# All_in_one_Starter_Kit_for_Arduino_V1_0.net
KiCad netlist of a schematic drawn in EAGLE
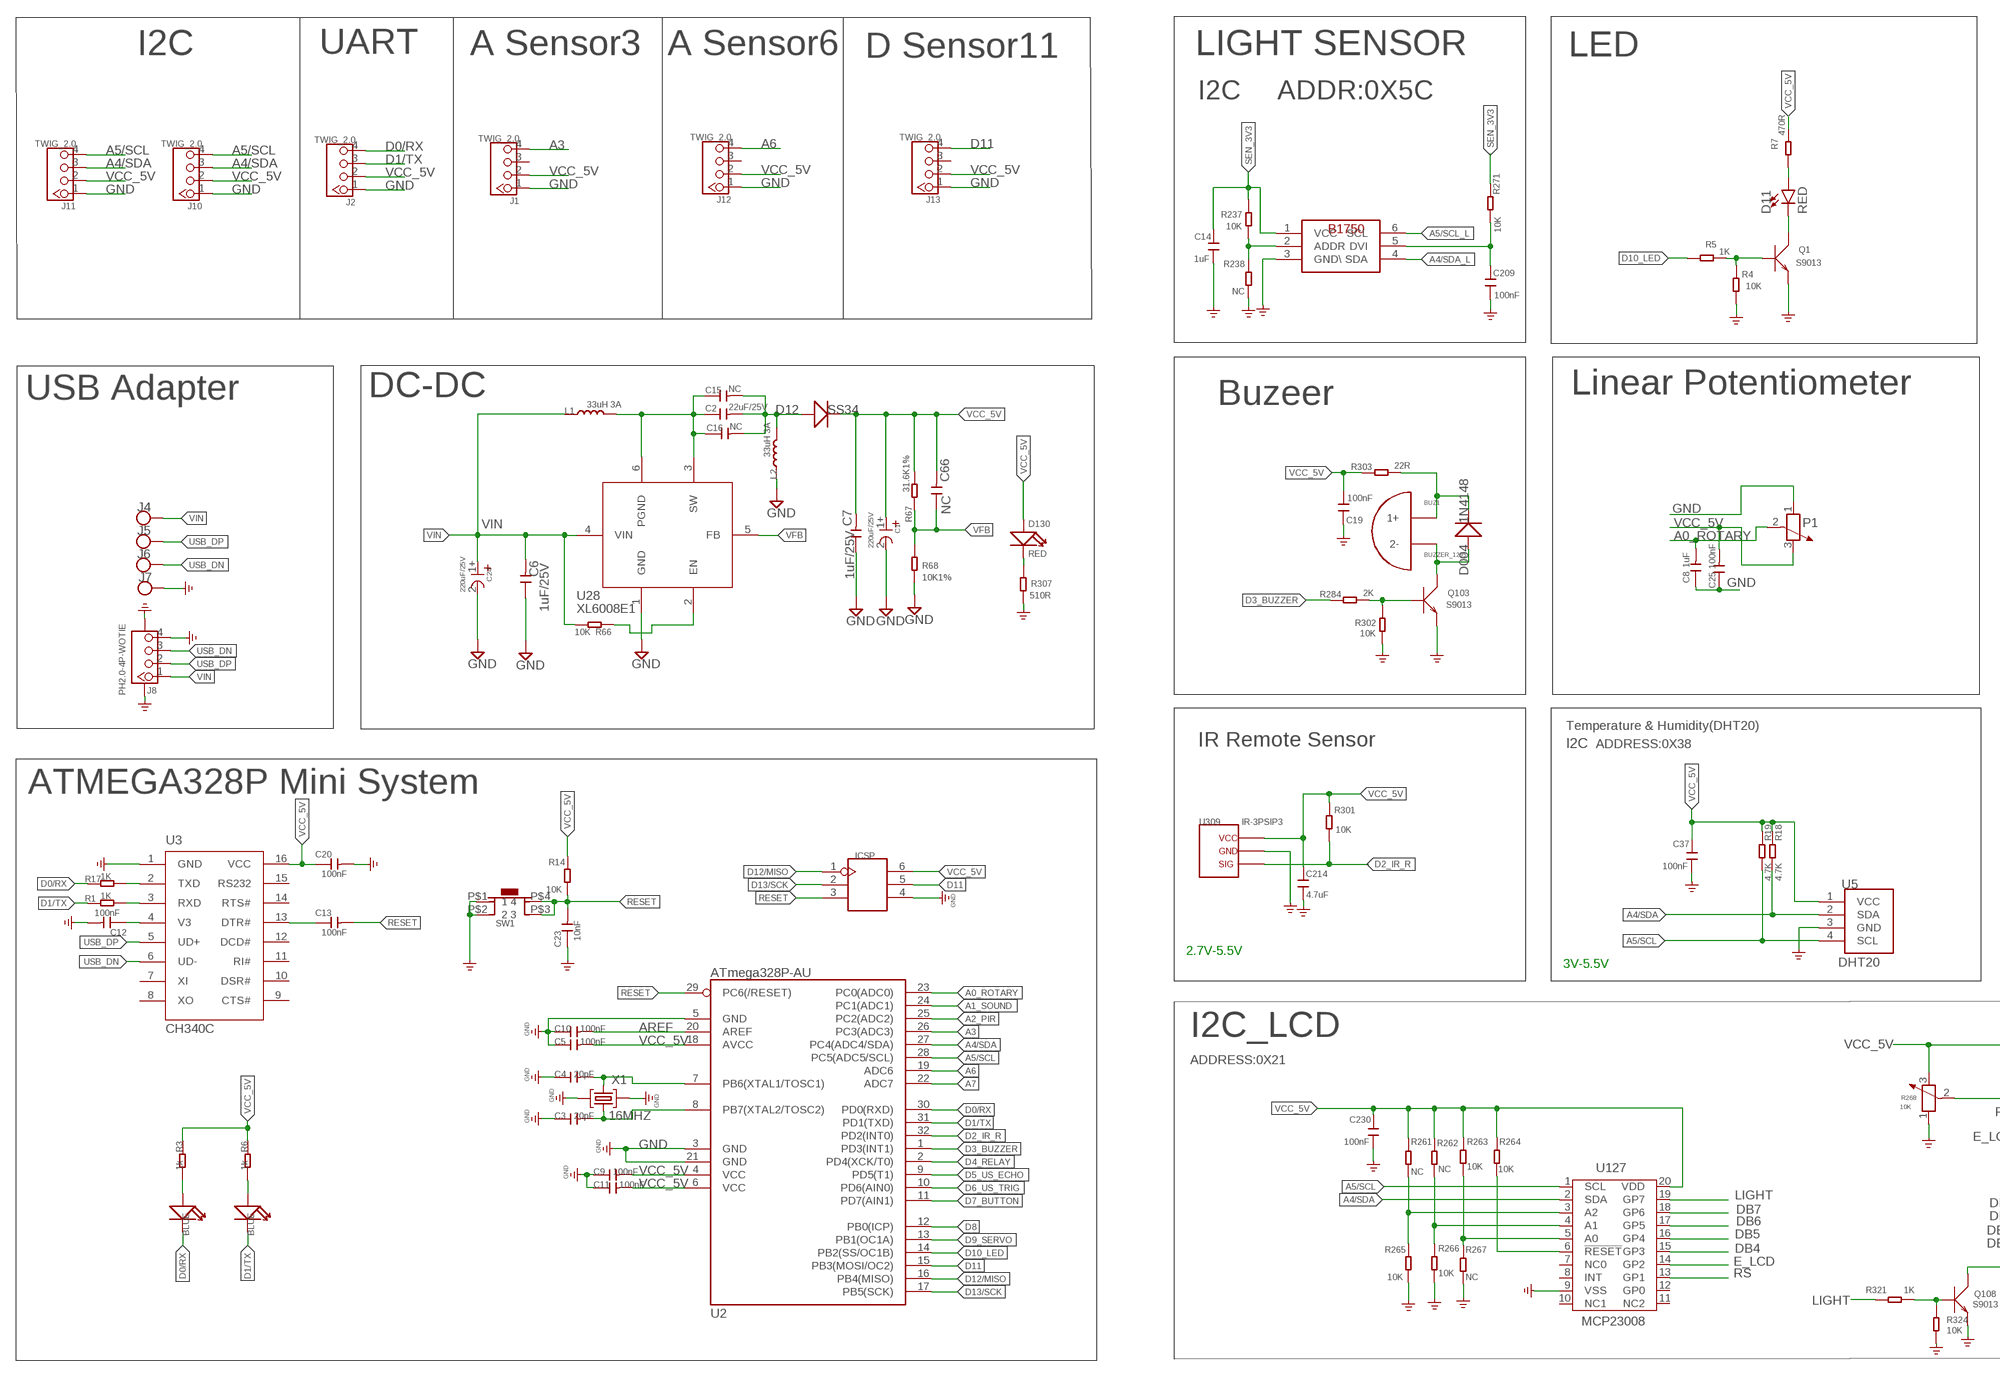
[diagram p0: schematic, sheet 1, part 1 of 2]
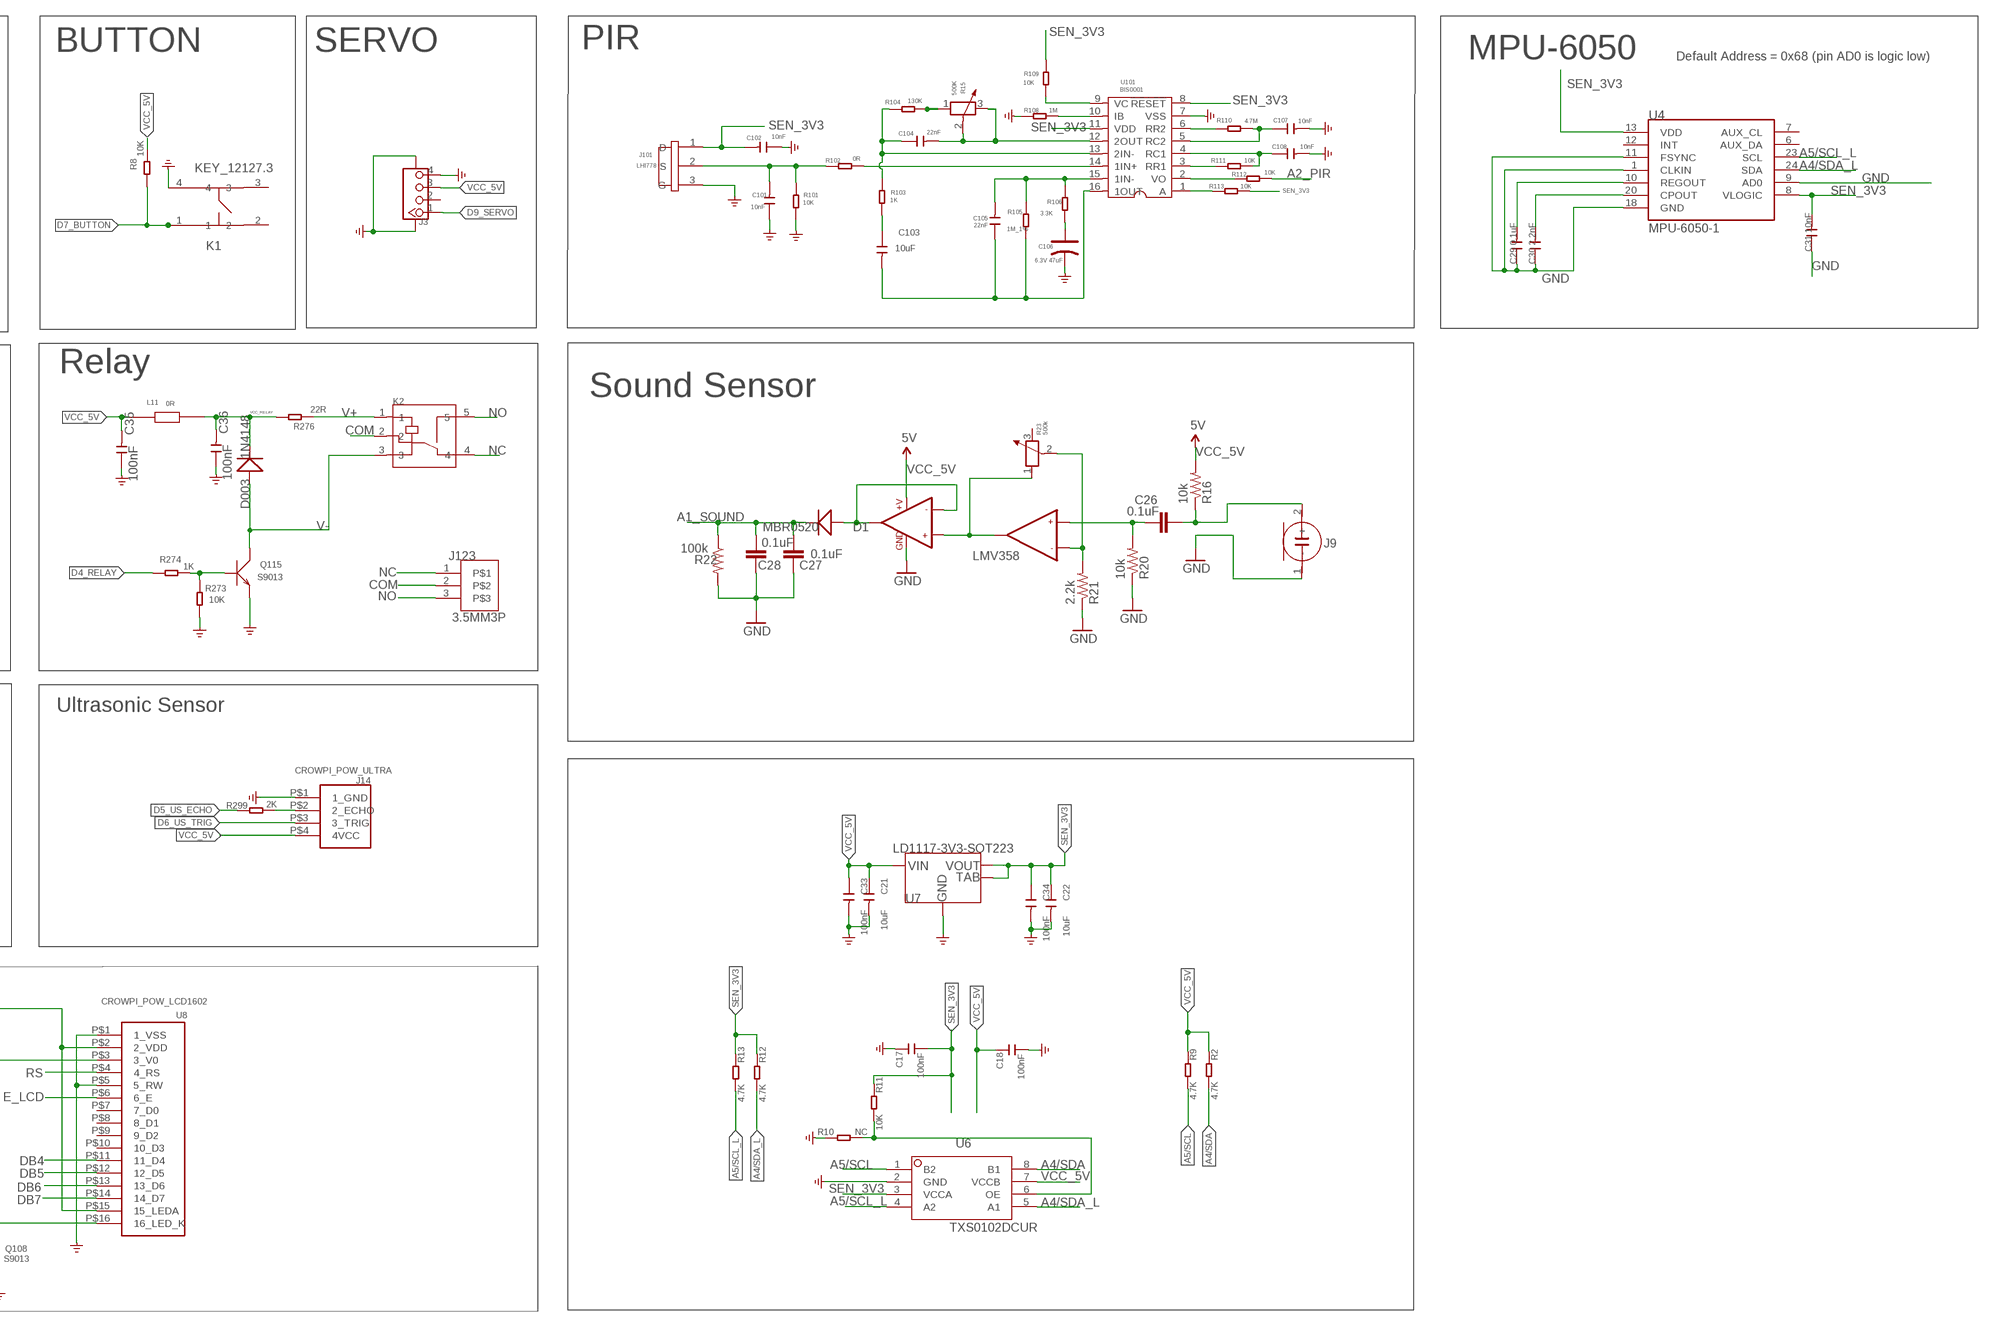
[diagram p1: schematic, sheet 1, part 2 of 2]

(export (version "E")
  (design (tool "Eeschema 10.0.6"))
  (components
    (comp (ref "BUZ1")
      (value "BUZZER_1295")
      (footprint "eagle-import:BUZZER-D12MM-DIP2")
      (libsource (lib "eagle-import") (part "BUZZERBUZZER_1295_DIP"))
    )
    (comp (ref "C1")
      (value "220uF/25V")
      (footprint "eagle-import:CAP_SMD_6.3_5.4MM")
      (libsource (lib "eagle-import") (part "CAP_SMD_6.35.4MM"))
    )
    (comp (ref "C2")
      (value "22uF/25V")
      (footprint "eagle-import:C0805")
      (libsource (lib "eagle-import") (part "CAPC0805"))
    )
    (comp (ref "C3")
      (value "20pF")
      (footprint "eagle-import:C0603")
      (libsource (lib "eagle-import") (part "C-0603"))
    )
    (comp (ref "C4")
      (value "20pF")
      (footprint "eagle-import:C0603")
      (libsource (lib "eagle-import") (part "C-0603"))
    )
    (comp (ref "C5")
      (value "100nF")
      (footprint "eagle-import:C0603")
      (libsource (lib "eagle-import") (part "C-0603"))
    )
    (comp (ref "C6")
      (value "1uF/25V")
      (footprint "eagle-import:C0603")
      (libsource (lib "eagle-import") (part "discrete_211_C-0603"))
    )
    (comp (ref "C7")
      (value "1uF/25V")
      (footprint "eagle-import:C0603")
      (libsource (lib "eagle-import") (part "discrete_211_C-0603"))
    )
    (comp (ref "C8")
      (value "1uF")
      (footprint "eagle-import:C0603")
      (libsource (lib "eagle-import") (part "C-0603"))
    )
    (comp (ref "C9")
      (value "100nF")
      (footprint "eagle-import:C0603")
      (libsource (lib "eagle-import") (part "C-0603"))
    )
    (comp (ref "C10")
      (value "100nF")
      (footprint "eagle-import:C0603")
      (libsource (lib "eagle-import") (part "C-0603"))
    )
    (comp (ref "C11")
      (value "100nF")
      (footprint "eagle-import:C0603")
      (libsource (lib "eagle-import") (part "C-0603"))
    )
    (comp (ref "C12")
      (value "100nF")
      (footprint "eagle-import:C0603")
      (libsource (lib "eagle-import") (part "Lora_Basic_Gateway_ Module_C0603"))
    )
    (comp (ref "C13")
      (value "100nF")
      (footprint "eagle-import:C0603")
      (libsource (lib "eagle-import") (part "Lora_Basic_Gateway_ Module_C0603"))
    )
    (comp (ref "C14")
      (value "1uF")
      (footprint "eagle-import:0603")
      (libsource (lib "eagle-import") (part "cooper_C0603"))
    )
    (comp (ref "C15")
      (value "NC")
      (footprint "eagle-import:C0805")
      (libsource (lib "eagle-import") (part "CAPC0805"))
    )
    (comp (ref "C16")
      (value "NC")
      (footprint "eagle-import:C0805")
      (libsource (lib "eagle-import") (part "CAPC0805"))
    )
    (comp (ref "C17")
      (value "100nF")
      (footprint "eagle-import:0603")
      (libsource (lib "eagle-import") (part "cooper_C0603"))
    )
    (comp (ref "C18")
      (value "100nF")
      (footprint "eagle-import:0603")
      (libsource (lib "eagle-import") (part "cooper_C0603"))
    )
    (comp (ref "C19")
      (value "100nF")
      (footprint "eagle-import:0603")
      (libsource (lib "eagle-import") (part "cooper_C0603"))
    )
    (comp (ref "C20")
      (value "100nF")
      (footprint "eagle-import:C0603")
      (libsource (lib "eagle-import") (part "Lora_Basic_Gateway_ Module_C0603"))
    )
    (comp (ref "C21")
      (value "10uF")
      (footprint "eagle-import:C0603")
      (libsource (lib "eagle-import") (part "LoraWAN_Gateway_Mainboard_CAP"))
    )
    (comp (ref "C22")
      (value "10uF")
      (footprint "eagle-import:C0603")
      (libsource (lib "eagle-import") (part "LoraWAN_Gateway_Mainboard_CAP"))
    )
    (comp (ref "C23")
      (value "10nF")
      (footprint "eagle-import:C0603")
      (libsource (lib "eagle-import") (part "Lora_Basic_Gateway_ Module_C0603"))
    )
    (comp (ref "C24")
      (value "220uF/25V")
      (footprint "eagle-import:CAP_SMD_6.3_5.4MM")
      (libsource (lib "eagle-import") (part "CAP_SMD_6.35.4MM"))
    )
    (comp (ref "C25")
      (value "100nF")
      (footprint "eagle-import:C0603")
      (libsource (lib "eagle-import") (part "C-0603"))
    )
    (comp (ref "C26")
      (value "0.1uF")
      (footprint "eagle-import:0603-CAP")
      (libsource (lib "eagle-import") (part "CAP0603-CAP"))
    )
    (comp (ref "C27")
      (value "0.1uF")
      (footprint "eagle-import:0603-CAP")
      (libsource (lib "eagle-import") (part "CAP0603-CAP"))
    )
    (comp (ref "C28")
      (value "0.1uF")
      (footprint "eagle-import:0603-CAP")
      (libsource (lib "eagle-import") (part "CAP0603-CAP"))
    )
    (comp (ref "C29")
      (value "0.1uF")
      (footprint "eagle-import:C0603")
      (libsource (lib "eagle-import") (part "C-0603"))
    )
    (comp (ref "C30")
      (value "2.2nF")
      (footprint "eagle-import:C0603")
      (libsource (lib "eagle-import") (part "C-0603"))
    )
    (comp (ref "C31")
      (value "10nF")
      (footprint "eagle-import:C0603")
      (libsource (lib "eagle-import") (part "C-0603"))
    )
    (comp (ref "C33")
      (value "100nF")
      (footprint "eagle-import:C0603")
      (libsource (lib "eagle-import") (part "LoraWAN_Gateway_Mainboard_CAP"))
    )
    (comp (ref "C34")
      (value "100nF")
      (footprint "eagle-import:C0603")
      (libsource (lib "eagle-import") (part "LoraWAN_Gateway_Mainboard_CAP"))
    )
    (comp (ref "C35")
      (value "100nF")
      (footprint "eagle-import:C0603")
      (libsource (lib "eagle-import") (part "C-0603"))
    )
    (comp (ref "C36")
      (value "100nF")
      (footprint "eagle-import:C0603")
      (libsource (lib "eagle-import") (part "C-0603"))
    )
    (comp (ref "C37")
      (value "100nF")
      (footprint "eagle-import:0603")
      (libsource (lib "eagle-import") (part "cooper_C0603"))
    )
    (comp (ref "C66")
      (value "NC")
      (footprint "eagle-import:C0603")
      (libsource (lib "eagle-import") (part "discrete_211_C-0603"))
    )
    (comp (ref "C101")
      (value "10nF")
      (footprint "eagle-import:C0603")
      (libsource (lib "eagle-import") (part "C-0603"))
    )
    (comp (ref "C102")
      (value "10nF")
      (footprint "eagle-import:C0603")
      (libsource (lib "eagle-import") (part "C-0603"))
    )
    (comp (ref "C103")
      (value "10uF")
      (footprint "eagle-import:0603")
      (libsource (lib "eagle-import") (part "C0603"))
    )
    (comp (ref "C104")
      (value "22nF")
      (footprint "eagle-import:C0603")
      (libsource (lib "eagle-import") (part "C-0603"))
    )
    (comp (ref "C105")
      (value "22nF")
      (footprint "eagle-import:C0603")
      (libsource (lib "eagle-import") (part "C-0603"))
    )
    (comp (ref "C106")
      (value "6.3V 47uF")
      (footprint "eagle-import:AVX-A")
      (libsource (lib "eagle-import") (part "CAP-AVX-A"))
    )
    (comp (ref "C107")
      (value "10nF")
      (footprint "eagle-import:C0603")
      (libsource (lib "eagle-import") (part "C-0603"))
    )
    (comp (ref "C108")
      (value "10nF")
      (footprint "eagle-import:C0603")
      (libsource (lib "eagle-import") (part "C-0603"))
    )
    (comp (ref "C209")
      (value "100nF")
      (footprint "eagle-import:0603")
      (libsource (lib "eagle-import") (part "cooper_C0603"))
    )
    (comp (ref "C214")
      (value "4.7uF")
      (footprint "eagle-import:0603")
      (libsource (lib "eagle-import") (part "cooper_C0603"))
    )
    (comp (ref "C230")
      (value "100nF")
      (footprint "eagle-import:0603")
      (libsource (lib "eagle-import") (part "cooper_C0603"))
    )
    (comp (ref "D1")
      (value "MBR0520")
      (footprint "eagle-import:SOD123-2.7X1.6")
      (libsource (lib "eagle-import") (part "D'MBR0520LT1'"))
    )
    (comp (ref "D003")
      (value "1N4148")
      (footprint "eagle-import:D_SOD123")
      (libsource (lib "eagle-import") (part "DIODE1206"))
    )
    (comp (ref "D004")
      (value "1N4148")
      (footprint "eagle-import:D_SOD123")
      (libsource (lib "eagle-import") (part "DIODE1206"))
    )
    (comp (ref "D11")
      (value "RED")
      (footprint "eagle-import:LED-8MM")
      (libsource (lib "eagle-import") (part "LED"))
    )
    (comp (ref "D12")
      (value "SS34")
      (footprint "eagle-import:SMA")
      (libsource (lib "eagle-import") (part "DIODEB130L-13-F"))
    )
    (comp (ref "D13")
      (value "BLUE")
      (footprint "eagle-import:LED-0603")
      (libsource (lib "eagle-import") (part "LED'0603'"))
    )
    (comp (ref "D14")
      (value "BLUE")
      (footprint "eagle-import:LED-0603")
      (libsource (lib "eagle-import") (part "LED'0603'"))
    )
    (comp (ref "D130")
      (value "RED")
      (footprint "eagle-import:LED_0603_SMT")
      (libsource (lib "eagle-import") (part "LED_0603_SMT"))
    )
    (comp (ref "ICSP")
      (value "2.54-2x3p male")
      (footprint "eagle-import:2X3P-2.54")
      (libsource (lib "eagle-import") (part "HEADER-2X3P-2.54"))
    )
    (comp (ref "J1")
      (value "TWIG_2.0")
      (footprint "eagle-import:2.0_1X4")
      (libsource (lib "eagle-import") (part "TWIG_2.0"))
    )
    (comp (ref "J2")
      (value "TWIG_2.0")
      (footprint "eagle-import:2.0_1X4")
      (libsource (lib "eagle-import") (part "TWIG_2.0"))
    )
    (comp (ref "J3")
      (value "A_XBJ_CONNECTOR_TWIG-4P-2.0-SMD-FEMALE-REINFORCE90D")
      (footprint "eagle-import:A_XBJ_CONNECTOR_4P-SMD-2.0-90D")
      (libsource (lib "eagle-import") (part "A_XBJ_CONNECTOR_TWIG-4P-2.0-SMD-FEMALE-REINFORCE90D"))
    )
    (comp (ref "J4")
      (value "TP-SMDTP-SMD-2X4MM")
      (footprint "eagle-import:TP-SMD-2X4MM")
      (libsource (lib "eagle-import") (part "TP-SMDTP-SMD-2X4MM"))
    )
    (comp (ref "J5")
      (value "TP-SMDTP-SMD-2X4MM")
      (footprint "eagle-import:TP-SMD-2X4MM")
      (libsource (lib "eagle-import") (part "TP-SMDTP-SMD-2X4MM"))
    )
    (comp (ref "J6")
      (value "TP-SMDTP-SMD-2X4MM")
      (footprint "eagle-import:TP-SMD-2X4MM")
      (libsource (lib "eagle-import") (part "TP-SMDTP-SMD-2X4MM"))
    )
    (comp (ref "J7")
      (value "TP-SMDTP-SMD-2X4MM")
      (footprint "eagle-import:TP-SMD-2X4MM")
      (libsource (lib "eagle-import") (part "TP-SMDTP-SMD-2X4MM"))
    )
    (comp (ref "J8")
      (value "PH2.0-4P-WOTIE")
      (footprint "eagle-import:PH2.0-4P")
      (libsource (lib "eagle-import") (part "PH2.0-4P-WOTIE"))
    )
    (comp (ref "J9")
      (value "TEMPLATE_MIC-6MM")
      (footprint "eagle-import:TEMPLATE_2P-D6MM")
      (libsource (lib "eagle-import") (part "TEMPLATE_MIC-6MM"))
    )
    (comp (ref "J10")
      (value "TWIG_2.0")
      (footprint "eagle-import:2.0_1X4")
      (libsource (lib "eagle-import") (part "TWIG_2.0"))
    )
    (comp (ref "J11")
      (value "TWIG_2.0")
      (footprint "eagle-import:2.0_1X4")
      (libsource (lib "eagle-import") (part "TWIG_2.0"))
    )
    (comp (ref "J12")
      (value "TWIG_2.0")
      (footprint "eagle-import:2.0_1X4")
      (libsource (lib "eagle-import") (part "TWIG_2.0"))
    )
    (comp (ref "J13")
      (value "TWIG_2.0")
      (footprint "eagle-import:2.0_1X4")
      (libsource (lib "eagle-import") (part "TWIG_2.0"))
    )
    (comp (ref "J14")
      (value "CROWPI_POW_ULTRA")
      (footprint "eagle-import:CROWPI_POW_ULTRA")
      (libsource (lib "eagle-import") (part "CROWPI_POW_ULTRA"))
    )
    (comp (ref "J101")
      (value "LHI778")
      (footprint "eagle-import:3P-D8.1MM")
      (libsource (lib "eagle-import") (part "LHI778"))
    )
    (comp (ref "J123")
      (value "3.5MM3P")
      (footprint "eagle-import:3.5MM_3P")
      (libsource (lib "eagle-import") (part "3.5MM3P"))
    )
    (comp (ref "K1")
      (value "KEY_12127.3")
      (footprint "eagle-import:KEY_12_12_7.3")
      (libsource (lib "eagle-import") (part "KEY_12127.3"))
    )
    (comp (ref "K2")
      (value "RELAY-SRD")
      (footprint "eagle-import:REY5-6-19.1X15.5X15.3MM")
      (libsource (lib "eagle-import") (part "RELAY-SRD"))
    )
    (comp (ref "L1")
      (value "33uH 3A")
      (footprint "eagle-import:L1040-SMD")
      (libsource (lib "eagle-import") (part "L"))
    )
    (comp (ref "L2")
      (value "33uH 3A")
      (footprint "eagle-import:L1040-SMD")
      (libsource (lib "eagle-import") (part "L"))
    )
    (comp (ref "L11")
      (value "0R")
      (footprint "eagle-import:201209")
      (libsource (lib "eagle-import") (part "CMP201209UD1R0MT201209"))
    )
    (comp (ref "P1")
      (value "R-POTENTIOMETER")
      (footprint "eagle-import:3P-SQUA-45.6X10X5.8H")
      (libsource (lib "eagle-import") (part "R-POTENTIOMETER"))
    )
    (comp (ref "Q1")
      (value "S9013")
      (footprint "eagle-import:SOT23@1")
      (libsource (lib "eagle-import") (part "TRANSISTOR-NPN-SOT23"))
    )
    (comp (ref "Q103")
      (value "S9013")
      (footprint "eagle-import:SOT23@1")
      (libsource (lib "eagle-import") (part "TRANSISTOR-NPN-SOT23"))
    )
    (comp (ref "Q108")
      (value "S9013")
      (footprint "eagle-import:SOT23@1")
      (libsource (lib "eagle-import") (part "TRANSISTOR-NPN-SOT23"))
    )
    (comp (ref "Q115")
      (value "S9013")
      (footprint "eagle-import:SOT23@1")
      (libsource (lib "eagle-import") (part "TRANSISTOR-NPN-SOT23"))
    )
    (comp (ref "R1")
      (value "1K")
      (footprint "eagle-import:R0603")
      (libsource (lib "eagle-import") (part "R0603"))
    )
    (comp (ref "R2")
      (value "4.7K")
      (footprint "eagle-import:R0603")
      (libsource (lib "eagle-import") (part "cooper_R0603"))
    )
    (comp (ref "R3")
      (value "1k")
      (footprint "eagle-import:R0603")
      (libsource (lib "eagle-import") (part "R-0603"))
    )
    (comp (ref "R4")
      (value "10K")
      (footprint "eagle-import:R0603")
      (libsource (lib "eagle-import") (part "R-0603"))
    )
    (comp (ref "R5")
      (value "1K")
      (footprint "eagle-import:R0603")
      (libsource (lib "eagle-import") (part "R-0603"))
    )
    (comp (ref "R6")
      (value "1k")
      (footprint "eagle-import:R0603")
      (libsource (lib "eagle-import") (part "R-0603"))
    )
    (comp (ref "R7")
      (value "470R")
      (footprint "eagle-import:R0603")
      (libsource (lib "eagle-import") (part "R-0603"))
    )
    (comp (ref "R8")
      (value "10K")
      (footprint "eagle-import:R0603")
      (libsource (lib "eagle-import") (part "R-0603"))
    )
    (comp (ref "R9")
      (value "4.7K")
      (footprint "eagle-import:R0603")
      (libsource (lib "eagle-import") (part "cooper_R0603"))
    )
    (comp (ref "R10")
      (value "NC")
      (footprint "eagle-import:R0603")
      (libsource (lib "eagle-import") (part "cooper_R0603"))
    )
    (comp (ref "R11")
      (value "10K")
      (footprint "eagle-import:R0603")
      (libsource (lib "eagle-import") (part "cooper_R0603"))
    )
    (comp (ref "R12")
      (value "4.7K")
      (footprint "eagle-import:R0603")
      (libsource (lib "eagle-import") (part "cooper_R0603"))
    )
    (comp (ref "R13")
      (value "4.7K")
      (footprint "eagle-import:R0603")
      (libsource (lib "eagle-import") (part "cooper_R0603"))
    )
    (comp (ref "R14")
      (value "10K")
      (footprint "eagle-import:R0603")
      (libsource (lib "eagle-import") (part "cooper_R0603"))
    )
    (comp (ref "R15")
      (value "500K")
      (footprint "eagle-import:3P-SMD-SQUA-3.6X3.3")
      (libsource (lib "eagle-import") (part "R-POTENTIOMETER-SMD"))
    )
    (comp (ref "R16")
      (value "10k")
      (footprint "eagle-import:0603-RES")
      (libsource (lib "eagle-import") (part "RESISTOR0603-RES"))
    )
    (comp (ref "R17")
      (value "1K")
      (footprint "eagle-import:R0603")
      (libsource (lib "eagle-import") (part "R0603"))
    )
    (comp (ref "R18")
      (value "4.7K")
      (footprint "eagle-import:R0603")
      (libsource (lib "eagle-import") (part "cooper_R0603"))
    )
    (comp (ref "R19")
      (value "4.7K")
      (footprint "eagle-import:R0603")
      (libsource (lib "eagle-import") (part "cooper_R0603"))
    )
    (comp (ref "R20")
      (value "10k")
      (footprint "eagle-import:0603-RES")
      (libsource (lib "eagle-import") (part "RESISTOR0603-RES"))
    )
    (comp (ref "R21")
      (value "2.2k")
      (footprint "eagle-import:0603-RES")
      (libsource (lib "eagle-import") (part "RESISTOR0603-RES"))
    )
    (comp (ref "R22")
      (value "100k")
      (footprint "eagle-import:0603-RES")
      (libsource (lib "eagle-import") (part "RESISTOR0603-RES"))
    )
    (comp (ref "R23")
      (value "500k")
      (footprint "eagle-import:3P-SMD-SQUA-3.6X3.3")
      (libsource (lib "eagle-import") (part "R-POTENTIOMETER-SMD"))
    )
    (comp (ref "R66")
      (value "10K")
      (footprint "eagle-import:R0603")
      (libsource (lib "eagle-import") (part "cooper_R0603"))
    )
    (comp (ref "R67")
      (value "31.6K1%")
      (footprint "eagle-import:R0603")
      (libsource (lib "eagle-import") (part "cooper_R0603"))
    )
    (comp (ref "R68")
      (value "10K1%")
      (footprint "eagle-import:R0603")
      (libsource (lib "eagle-import") (part "cooper_R0603"))
    )
    (comp (ref "R101")
      (value "10K")
      (footprint "eagle-import:R0603")
      (libsource (lib "eagle-import") (part "R-0603"))
    )
    (comp (ref "R102")
      (value "0R")
      (footprint "eagle-import:R0603")
      (libsource (lib "eagle-import") (part "R-0603"))
    )
    (comp (ref "R103")
      (value "1K")
      (footprint "eagle-import:R0603")
      (libsource (lib "eagle-import") (part "R-0603"))
    )
    (comp (ref "R104")
      (value "130K")
      (footprint "eagle-import:R0603")
      (libsource (lib "eagle-import") (part "R-0603"))
    )
    (comp (ref "R105")
      (value "1M_1%")
      (footprint "eagle-import:R0603")
      (libsource (lib "eagle-import") (part "R-0603"))
    )
    (comp (ref "R106")
      (value "3.3K")
      (footprint "eagle-import:R0603")
      (libsource (lib "eagle-import") (part "R-0603"))
    )
    (comp (ref "R108")
      (value "1M")
      (footprint "eagle-import:R0603")
      (libsource (lib "eagle-import") (part "R-0603"))
    )
    (comp (ref "R109")
      (value "10K")
      (footprint "eagle-import:R0603")
      (libsource (lib "eagle-import") (part "R-0603"))
    )
    (comp (ref "R110")
      (value "4.7M")
      (footprint "eagle-import:R0603")
      (libsource (lib "eagle-import") (part "R-0603"))
    )
    (comp (ref "R111")
      (value "10K")
      (footprint "eagle-import:R0603")
      (libsource (lib "eagle-import") (part "R-0603"))
    )
    (comp (ref "R112")
      (value "10K")
      (footprint "eagle-import:R0603")
      (libsource (lib "eagle-import") (part "R-0603"))
    )
    (comp (ref "R113")
      (value "10K")
      (footprint "eagle-import:R0603")
      (libsource (lib "eagle-import") (part "R-0603"))
    )
    (comp (ref "R237")
      (value "10K")
      (footprint "eagle-import:R0603")
      (libsource (lib "eagle-import") (part "cooper_R0603"))
    )
    (comp (ref "R238")
      (value "NC")
      (footprint "eagle-import:R0603")
      (libsource (lib "eagle-import") (part "cooper_R0603"))
    )
    (comp (ref "R261")
      (value "NC")
      (footprint "eagle-import:R0603")
      (libsource (lib "eagle-import") (part "cooper_R0603"))
    )
    (comp (ref "R262")
      (value "NC")
      (footprint "eagle-import:R0603")
      (libsource (lib "eagle-import") (part "cooper_R0603"))
    )
    (comp (ref "R263")
      (value "10K")
      (footprint "eagle-import:R0603")
      (libsource (lib "eagle-import") (part "cooper_R0603"))
    )
    (comp (ref "R264")
      (value "10K")
      (footprint "eagle-import:R0603")
      (libsource (lib "eagle-import") (part "cooper_R0603"))
    )
    (comp (ref "R265")
      (value "10K")
      (footprint "eagle-import:R0603")
      (libsource (lib "eagle-import") (part "cooper_R0603"))
    )
    (comp (ref "R266")
      (value "10K")
      (footprint "eagle-import:R0603")
      (libsource (lib "eagle-import") (part "cooper_R0603"))
    )
    (comp (ref "R267")
      (value "NC")
      (footprint "eagle-import:R0603")
      (libsource (lib "eagle-import") (part "cooper_R0603"))
    )
    (comp (ref "R268")
      (value "10K")
      (footprint "eagle-import:3P-SMD-SQUA-3.6X3.3")
      (libsource (lib "eagle-import") (part "R-POTENTIOMETER-SMD"))
    )
    (comp (ref "R271")
      (value "10K")
      (footprint "eagle-import:R0603")
      (libsource (lib "eagle-import") (part "cooper_R0603"))
    )
    (comp (ref "R273")
      (value "10K")
      (footprint "eagle-import:R0603")
      (libsource (lib "eagle-import") (part "R-0603"))
    )
    (comp (ref "R274")
      (value "1K")
      (footprint "eagle-import:R0603")
      (libsource (lib "eagle-import") (part "R-0603"))
    )
    (comp (ref "R276")
      (value "22R")
      (footprint "eagle-import:R0603")
      (libsource (lib "eagle-import") (part "R-0603"))
    )
    (comp (ref "R284")
      (value "2K")
      (footprint "eagle-import:R0603")
      (libsource (lib "eagle-import") (part "cooper_R0603"))
    )
    (comp (ref "R299")
      (value "2K")
      (footprint "eagle-import:R0603")
      (libsource (lib "eagle-import") (part "cooper_R0603"))
    )
    (comp (ref "R301")
      (value "10K")
      (footprint "eagle-import:R0603")
      (libsource (lib "eagle-import") (part "cooper_R0603"))
    )
    (comp (ref "R302")
      (value "10K")
      (footprint "eagle-import:R0603")
      (libsource (lib "eagle-import") (part "cooper_R0603"))
    )
    (comp (ref "R303")
      (value "22R")
      (footprint "eagle-import:R0603")
      (libsource (lib "eagle-import") (part "cooper_R0603"))
    )
    (comp (ref "R307")
      (value "510R")
      (footprint "eagle-import:R0603")
      (libsource (lib "eagle-import") (part "cooper_R0603"))
    )
    (comp (ref "R321")
      (value "1K")
      (footprint "eagle-import:R0603")
      (libsource (lib "eagle-import") (part "cooper_R0603"))
    )
    (comp (ref "R324")
      (value "10K")
      (footprint "eagle-import:R0603")
      (libsource (lib "eagle-import") (part "cooper_R0603"))
    )
    (comp (ref "SW1")
      (value "BUTTON-4P-SMD4.2X3.2")
      (footprint "eagle-import:BUTTON-SMD4P-4.2X3.2X2.5")
      (libsource (lib "eagle-import") (part "BUTTON-4P-SMD4.2X3.2"))
    )
    (comp (ref "U1")
      (value "LMV358")
      (footprint "eagle-import:SO08")
      (libsource (lib "eagle-import") (part "LMV358"))
    )
    (comp (ref "U2")
      (value "ATmega328P-AU")
      (footprint "eagle-import:TQFP32")
      (libsource (lib "eagle-import") (part "ATMEGA168"))
    )
    (comp (ref "U3")
      (value "CH340C")
      (footprint "eagle-import:SOP-16")
      (libsource (lib "eagle-import") (part "CH340G"))
    )
    (comp (ref "U4")
      (value "MPU-6050-1")
      (footprint "eagle-import:QFN-24-4MM2")
      (libsource (lib "eagle-import") (part "MPU-6050-1"))
    )
    (comp (ref "U5")
      (value "DHT20")
      (footprint "eagle-import:CROWTAIL-DHT20-V1.0-20211013_DHT20")
      (libsource (lib "eagle-import") (part "CROWTAIL-DHT20-V1.0-20211013_DHT20"))
    )
    (comp (ref "U6")
      (value "TXS0102DCUR")
      (footprint "eagle-import:VSSOP-8")
      (libsource (lib "eagle-import") (part "TXS0102DCUR"))
    )
    (comp (ref "U7")
      (value "LD1117-3V3-SOT223")
      (footprint "eagle-import:SOT223")
      (libsource (lib "eagle-import") (part "LD1117-3V3-SOT223"))
    )
    (comp (ref "U8")
      (value "CROWPI_POW_LCD1602")
      (footprint "eagle-import:CROWPI_POW_LCD1206")
      (libsource (lib "eagle-import") (part "CROWPI_POW_LCD1602"))
    )
    (comp (ref "U28")
      (value "XL6008E1")
      (footprint "eagle-import:TO252-5")
      (libsource (lib "eagle-import") (part "XL6008XL6008"))
    )
    (comp (ref "U101")
      (value "BIS0001")
      (footprint "eagle-import:SOP16")
      (libsource (lib "eagle-import") (part "TM2291"))
    )
    (comp (ref "U121")
      (value "BH1750")
      (footprint "eagle-import:BH1750-WSOF-6")
      (libsource (lib "eagle-import") (part "BH1750"))
    )
    (comp (ref "U127")
      (value "MCP23008")
      (footprint "eagle-import:SSOP20")
      (libsource (lib "eagle-import") (part "MCP23008"))
    )
    (comp (ref "U309")
      (value "IR-3PSIP3")
      (footprint "eagle-import:VS1838B-SIP3")
      (libsource (lib "eagle-import") (part "IR-3PSIP3"))
    )
    (comp (ref "X1")
      (value "16MHZ")
      (footprint "eagle-import:CRYSTAL-3.2-2.5")
      (libsource (lib "eagle-import") (part "CRYSTAL-3.2-2.5"))
    )
  )
  (nets
    (net (code "1") (name "/AREF") (class "Default")
      (node (ref "C10") (pin "2") (pinfunction "2_2") (pintype "passive"))
      (node (ref "U2") (pin "20") (pinfunction "AREF_20") (pintype "bidirectional"))
    )
    (net (code "2") (name "/COM") (class "Default")
      (node (ref "J123") (pin "2") (pinfunction "P$2_2") (pintype "bidirectional"))
      (node (ref "K2") (pin "2") (pinfunction "2_2") (pintype "bidirectional"))
    )
    (net (code "3") (name "/DB4") (class "Default")
      (node (ref "U127") (pin "15") (pinfunction "GP3_15") (pintype "bidirectional"))
      (node (ref "U8") (pin "P$11") (pinfunction "11_D4_P$11") (pintype "bidirectional"))
    )
    (net (code "4") (name "/DB5") (class "Default")
      (node (ref "U127") (pin "16") (pinfunction "GP4_16") (pintype "bidirectional"))
      (node (ref "U8") (pin "P$12") (pinfunction "12_D5_P$12") (pintype "bidirectional"))
    )
    (net (code "5") (name "/DB6") (class "Default")
      (node (ref "U127") (pin "17") (pinfunction "GP5_17") (pintype "bidirectional"))
      (node (ref "U8") (pin "P$13") (pinfunction "13_D6_P$13") (pintype "bidirectional"))
    )
    (net (code "6") (name "/DB7") (class "Default")
      (node (ref "U127") (pin "18") (pinfunction "GP6_18") (pintype "bidirectional"))
      (node (ref "U8") (pin "P$14") (pinfunction "14_D7_P$14") (pintype "bidirectional"))
    )
    (net (code "7") (name "/E_LCD") (class "Default")
      (node (ref "U127") (pin "14") (pinfunction "GP2_14") (pintype "bidirectional"))
      (node (ref "U8") (pin "P$6") (pinfunction "6_E_P$6") (pintype "bidirectional"))
    )
    (net (code "8") (name "/LIGHT") (class "Default")
      (node (ref "R321") (pin "2") (pinfunction "2_2") (pintype "passive"))
      (node (ref "U127") (pin "19") (pinfunction "GP7_19") (pintype "bidirectional"))
    )
    (net (code "9") (name "/NC") (class "Default")
      (node (ref "J123") (pin "1") (pinfunction "P$1_1") (pintype "bidirectional"))
      (node (ref "K2") (pin "4") (pinfunction "4_4") (pintype "bidirectional"))
    )
    (net (code "10") (name "/NO") (class "Default")
      (node (ref "J123") (pin "3") (pinfunction "P$3_3") (pintype "bidirectional"))
      (node (ref "K2") (pin "5") (pinfunction "5_5") (pintype "bidirectional"))
    )
    (net (code "11") (name "/RS") (class "Default")
      (node (ref "U127") (pin "13") (pinfunction "GP1_13") (pintype "bidirectional"))
      (node (ref "U8") (pin "P$4") (pinfunction "4_RS_P$4") (pintype "bidirectional"))
    )
    (net (code "12") (name "/V+") (class "Default")
      (node (ref "K2") (pin "1") (pinfunction "1_1") (pintype "bidirectional"))
      (node (ref "R276") (pin "2") (pinfunction "2_2") (pintype "passive"))
    )
    (net (code "13") (name "/V-") (class "Default")
      (node (ref "D003") (pin "+") (pinfunction "+_+") (pintype "passive"))
      (node (ref "K2") (pin "3") (pinfunction "3_3") (pintype "bidirectional"))
      (node (ref "Q115") (pin "3") (pinfunction "C_3") (pintype "passive"))
    )
    (net (code "14") (name "/VCC_RELAY") (class "Default")
      (node (ref "C36") (pin "2") (pinfunction "2_2") (pintype "passive"))
      (node (ref "D003") (pin "-") (pinfunction "-_-") (pintype "passive"))
      (node (ref "L11") (pin "2") (pinfunction "2_2") (pintype "bidirectional"))
      (node (ref "R276") (pin "1") (pinfunction "1_1") (pintype "passive"))
    )
    (net (code "15") (name "A0_ROTARY") (class "Default")
      (node (ref "C8") (pin "2") (pinfunction "2_2") (pintype "passive"))
      (node (ref "P1") (pin "2") (pinfunction "3_2") (pintype "passive"))
      (node (ref "U2") (pin "23") (pinfunction "PC0(ADC0)_23") (pintype "bidirectional"))
    )
    (net (code "16") (name "A1_SOUND") (class "Default")
      (node (ref "C27") (pin "2") (pinfunction "2_2") (pintype "passive"))
      (node (ref "C28") (pin "2") (pinfunction "2_2") (pintype "passive"))
      (node (ref "D1") (pin "2") (pinfunction "-_2") (pintype "passive"))
      (node (ref "R22") (pin "1") (pinfunction "1_1") (pintype "passive"))
      (node (ref "U2") (pin "24") (pinfunction "PC1(ADC1)_24") (pintype "bidirectional"))
    )
    (net (code "17") (name "A2_PIR") (class "Default")
      (node (ref "R112") (pin "1") (pinfunction "1_1") (pintype "passive"))
      (node (ref "U2") (pin "25") (pinfunction "PC2(ADC2)_25") (pintype "bidirectional"))
    )
    (net (code "18") (name "A3") (class "Default")
      (node (ref "J1") (pin "4") (pinfunction "4_4") (pintype "bidirectional"))
      (node (ref "U2") (pin "26") (pinfunction "PC3(ADC3)_26") (pintype "bidirectional"))
    )
    (net (code "19") (name "A4{slash}SDA") (class "Default")
      (node (ref "J10") (pin "3") (pinfunction "3_3") (pintype "bidirectional"))
      (node (ref "J11") (pin "3") (pinfunction "3_3") (pintype "bidirectional"))
      (node (ref "R18") (pin "2") (pinfunction "2_2") (pintype "passive"))
      (node (ref "R2") (pin "2") (pinfunction "2_2") (pintype "passive"))
      (node (ref "U127") (pin "2") (pinfunction "SDA_2") (pintype "bidirectional"))
      (node (ref "U2") (pin "27") (pinfunction "PC4(ADC4/SDA)_27") (pintype "bidirectional"))
      (node (ref "U5") (pin "2") (pinfunction "SDA_2") (pintype "bidirectional"))
      (node (ref "U6") (pin "8") (pinfunction "B1_8") (pintype "bidirectional"))
    )
    (net (code "20") (name "A4{slash}SDA_L") (class "Default")
      (node (ref "R12") (pin "2") (pinfunction "2_2") (pintype "passive"))
      (node (ref "U121") (pin "4") (pinfunction "SDA_4") (pintype "bidirectional"))
      (node (ref "U4") (pin "24") (pinfunction "SDA_24") (pintype "bidirectional"))
      (node (ref "U6") (pin "5") (pinfunction "A1_5") (pintype "bidirectional"))
    )
    (net (code "21") (name "A5{slash}SCL") (class "Default")
      (node (ref "J10") (pin "4") (pinfunction "4_4") (pintype "bidirectional"))
      (node (ref "J11") (pin "4") (pinfunction "4_4") (pintype "bidirectional"))
      (node (ref "R19") (pin "2") (pinfunction "2_2") (pintype "passive"))
      (node (ref "R9") (pin "2") (pinfunction "2_2") (pintype "passive"))
      (node (ref "U127") (pin "1") (pinfunction "SCL_1") (pintype "bidirectional"))
      (node (ref "U2") (pin "28") (pinfunction "PC5(ADC5/SCL)_28") (pintype "bidirectional"))
      (node (ref "U5") (pin "4") (pinfunction "SCL_4") (pintype "bidirectional"))
      (node (ref "U6") (pin "1") (pinfunction "B2_1") (pintype "bidirectional"))
    )
    (net (code "22") (name "A5{slash}SCL_L") (class "Default")
      (node (ref "R13") (pin "2") (pinfunction "2_2") (pintype "passive"))
      (node (ref "U121") (pin "6") (pinfunction "SCL_6") (pintype "bidirectional"))
      (node (ref "U4") (pin "23") (pinfunction "SCL_23") (pintype "bidirectional"))
      (node (ref "U6") (pin "4") (pinfunction "A2_4") (pintype "bidirectional"))
    )
    (net (code "23") (name "A6") (class "Default")
      (node (ref "J12") (pin "4") (pinfunction "4_4") (pintype "bidirectional"))
      (node (ref "U2") (pin "19") (pinfunction "ADC6_19") (pintype "bidirectional"))
    )
    (net (code "24") (name "A7") (class "Default")
      (node (ref "U2") (pin "22") (pinfunction "ADC7_22") (pintype "bidirectional"))
    )
    (net (code "25") (name "D0{slash}RX") (class "Default")
      (node (ref "D13") (pin "-") (pinfunction "-_-") (pintype "passive"))
      (node (ref "J2") (pin "4") (pinfunction "4_4") (pintype "bidirectional"))
      (node (ref "R17") (pin "1") (pinfunction "1_1") (pintype "passive"))
      (node (ref "U2") (pin "30") (pinfunction "PD0(RXD)_30") (pintype "bidirectional"))
    )
    (net (code "26") (name "D1{slash}TX") (class "Default")
      (node (ref "D14") (pin "-") (pinfunction "-_-") (pintype "passive"))
      (node (ref "J2") (pin "3") (pinfunction "3_3") (pintype "bidirectional"))
      (node (ref "R1") (pin "1") (pinfunction "1_1") (pintype "passive"))
      (node (ref "U2") (pin "31") (pinfunction "PD1(TXD)_31") (pintype "bidirectional"))
    )
    (net (code "27") (name "D2_IR_R") (class "Default")
      (node (ref "R301") (pin "2") (pinfunction "2_2") (pintype "passive"))
      (node (ref "U2") (pin "32") (pinfunction "PD2(INT0)_32") (pintype "bidirectional"))
      (node (ref "U309") (pin "3") (pinfunction "P$3_3") (pintype "bidirectional"))
    )
    (net (code "28") (name "D3_BUZZER") (class "Default")
      (node (ref "R284") (pin "1") (pinfunction "1_1") (pintype "passive"))
      (node (ref "U2") (pin "1") (pinfunction "PD3(INT1)_1") (pintype "bidirectional"))
    )
    (net (code "29") (name "D4_RELAY") (class "Default")
      (node (ref "R274") (pin "2") (pinfunction "2_2") (pintype "passive"))
      (node (ref "U2") (pin "2") (pinfunction "PD4(XCK/T0)_2") (pintype "bidirectional"))
    )
    (net (code "30") (name "D5_US_ECHO") (class "Default")
      (node (ref "R299") (pin "2") (pinfunction "2_2") (pintype "passive"))
      (node (ref "U2") (pin "9") (pinfunction "PD5(T1)_9") (pintype "bidirectional"))
    )
    (net (code "31") (name "D6_US_TRIG") (class "Default")
      (node (ref "J14") (pin "P$3") (pinfunction "3_TRIG_P$3") (pintype "bidirectional"))
      (node (ref "U2") (pin "10") (pinfunction "PD6(AIN0)_10") (pintype "bidirectional"))
    )
    (net (code "32") (name "D7_BUTTON") (class "Default")
      (node (ref "K1") (pin "1") (pinfunction "1_1") (pintype "bidirectional"))
      (node (ref "R8") (pin "2") (pinfunction "2_2") (pintype "passive"))
      (node (ref "U2") (pin "11") (pinfunction "PD7(AIN1)_11") (pintype "bidirectional"))
    )
    (net (code "33") (name "D8") (class "Default")
      (node (ref "U2") (pin "12") (pinfunction "PB0(ICP)_12") (pintype "bidirectional"))
    )
    (net (code "34") (name "D9_SERVO") (class "Default")
      (node (ref "J3") (pin "1") (pinfunction "1_1") (pintype "bidirectional"))
      (node (ref "U2") (pin "13") (pinfunction "PB1(OC1A)_13") (pintype "bidirectional"))
    )
    (net (code "35") (name "D10_LED") (class "Default")
      (node (ref "R5") (pin "2") (pinfunction "2_2") (pintype "passive"))
      (node (ref "U2") (pin "14") (pinfunction "PB2(SS/OC1B)_14") (pintype "bidirectional"))
    )
    (net (code "36") (name "D11") (class "Default")
      (node (ref "ICSP") (pin "5") (pinfunction "5_5") (pintype "bidirectional"))
      (node (ref "J13") (pin "4") (pinfunction "4_4") (pintype "bidirectional"))
      (node (ref "U2") (pin "15") (pinfunction "PB3(MOSI/OC2)_15") (pintype "bidirectional"))
    )
    (net (code "37") (name "D12{slash}MISO") (class "Default")
      (node (ref "ICSP") (pin "1") (pinfunction "1_1") (pintype "bidirectional"))
      (node (ref "U2") (pin "16") (pinfunction "PB4(MISO)_16") (pintype "bidirectional"))
    )
    (net (code "38") (name "D13{slash}SCK") (class "Default")
      (node (ref "ICSP") (pin "2") (pinfunction "2_2") (pintype "bidirectional"))
      (node (ref "U2") (pin "17") (pinfunction "PB5(SCK)_17") (pintype "bidirectional"))
    )
    (net (code "39") (name "GND") (class "Default")
      (node (ref "C1") (pin "2-") (pinfunction "2-_2-") (pintype "bidirectional"))
      (node (ref "C10") (pin "1") (pinfunction "1_1") (pintype "passive"))
      (node (ref "C101") (pin "1") (pinfunction "1_1") (pintype "passive"))
      (node (ref "C102") (pin "1") (pinfunction "1_1") (pintype "passive"))
      (node (ref "C106") (pin "-") (pinfunction "-_-") (pintype "passive"))
      (node (ref "C107") (pin "2") (pinfunction "2_2") (pintype "passive"))
      (node (ref "C108") (pin "2") (pinfunction "2_2") (pintype "passive"))
      (node (ref "C11") (pin "1") (pinfunction "1_1") (pintype "passive"))
      (node (ref "C12") (pin "2") (pinfunction "2_2") (pintype "passive"))
      (node (ref "C14") (pin "1") (pinfunction "1_1") (pintype "passive"))
      (node (ref "C17") (pin "2") (pinfunction "2_2") (pintype "passive"))
      (node (ref "C18") (pin "1") (pinfunction "1_1") (pintype "passive"))
      (node (ref "C19") (pin "2") (pinfunction "2_2") (pintype "passive"))
      (node (ref "C20") (pin "2") (pinfunction "2_2") (pintype "passive"))
      (node (ref "C209") (pin "1") (pinfunction "1_1") (pintype "passive"))
      (node (ref "C21") (pin "2") (pinfunction "2_2") (pintype "passive"))
      (node (ref "C214") (pin "1") (pinfunction "1_1") (pintype "passive"))
      (node (ref "C22") (pin "2") (pinfunction "2_2") (pintype "passive"))
      (node (ref "C23") (pin "1") (pinfunction "1_1") (pintype "passive"))
      (node (ref "C230") (pin "1") (pinfunction "1_1") (pintype "passive"))
      (node (ref "C24") (pin "2-") (pinfunction "2-_2-") (pintype "bidirectional"))
      (node (ref "C25") (pin "1") (pinfunction "1_1") (pintype "passive"))
      (node (ref "C27") (pin "1") (pinfunction "1_1") (pintype "passive"))
      (node (ref "C28") (pin "1") (pinfunction "1_1") (pintype "passive"))
      (node (ref "C29") (pin "1") (pinfunction "1_1") (pintype "passive"))
      (node (ref "C3") (pin "1") (pinfunction "1_1") (pintype "passive"))
      (node (ref "C30") (pin "1") (pinfunction "1_1") (pintype "passive"))
      (node (ref "C31") (pin "1") (pinfunction "1_1") (pintype "passive"))
      (node (ref "C33") (pin "2") (pinfunction "2_2") (pintype "passive"))
      (node (ref "C34") (pin "2") (pinfunction "2_2") (pintype "passive"))
      (node (ref "C35") (pin "1") (pinfunction "1_1") (pintype "passive"))
      (node (ref "C36") (pin "1") (pinfunction "1_1") (pintype "passive"))
      (node (ref "C37") (pin "1") (pinfunction "1_1") (pintype "passive"))
      (node (ref "C4") (pin "1") (pinfunction "1_1") (pintype "passive"))
      (node (ref "C5") (pin "1") (pinfunction "1_1") (pintype "passive"))
      (node (ref "C6") (pin "1") (pinfunction "1_1") (pintype "passive"))
      (node (ref "C7") (pin "1") (pinfunction "1_1") (pintype "passive"))
      (node (ref "C8") (pin "1") (pinfunction "1_1") (pintype "passive"))
      (node (ref "C9") (pin "1") (pinfunction "1_1") (pintype "passive"))
      (node (ref "ICSP") (pin "4") (pinfunction "4_4") (pintype "bidirectional"))
      (node (ref "J1") (pin "1") (pinfunction "1_1") (pintype "bidirectional"))
      (node (ref "J10") (pin "1") (pinfunction "1_1") (pintype "bidirectional"))
      (node (ref "J101") (pin "3") (pinfunction "G_3") (pintype "bidirectional"))
      (node (ref "J11") (pin "1") (pinfunction "1_1") (pintype "bidirectional"))
      (node (ref "J12") (pin "1") (pinfunction "1_1") (pintype "bidirectional"))
      (node (ref "J13") (pin "1") (pinfunction "1_1") (pintype "bidirectional"))
      (node (ref "J14") (pin "P$1") (pinfunction "1_GND_P$1") (pintype "bidirectional"))
      (node (ref "J2") (pin "1") (pinfunction "1_1") (pintype "bidirectional"))
      (node (ref "J3") (pin "4") (pinfunction "4_4") (pintype "bidirectional"))
      (node (ref "J3") (pin "SS1") (pinfunction "SS1_SS1") (pintype "bidirectional"))
      (node (ref "J3") (pin "SS2") (pinfunction "SS2_SS2") (pintype "bidirectional"))
      (node (ref "J7") (pin "1") (pinfunction "1_1") (pintype "bidirectional"))
      (node (ref "J8") (pin "4") (pinfunction "4_4") (pintype "bidirectional"))
      (node (ref "J8") (pin "5") (pinfunction "SS1_5") (pintype "bidirectional"))
      (node (ref "J8") (pin "6") (pinfunction "SS2_6") (pintype "bidirectional"))
      (node (ref "J9") (pin "1") (pinfunction "-_1") (pintype "bidirectional"))
      (node (ref "K1") (pin "4") (pinfunction "4_4") (pintype "bidirectional"))
      (node (ref "L2") (pin "1") (pinfunction "1_1") (pintype "passive"))
      (node (ref "P1") (pin "1") (pinfunction "1_1") (pintype "passive"))
      (node (ref "Q1") (pin "2") (pinfunction "E_2") (pintype "passive"))
      (node (ref "Q103") (pin "2") (pinfunction "E_2") (pintype "passive"))
      (node (ref "Q108") (pin "2") (pinfunction "E_2") (pintype "passive"))
      (node (ref "Q115") (pin "2") (pinfunction "E_2") (pintype "passive"))
      (node (ref "R10") (pin "1") (pinfunction "1_1") (pintype "passive"))
      (node (ref "R101") (pin "1") (pinfunction "1_1") (pintype "passive"))
      (node (ref "R108") (pin "1") (pinfunction "1_1") (pintype "passive"))
      (node (ref "R20") (pin "1") (pinfunction "1_1") (pintype "passive"))
      (node (ref "R21") (pin "1") (pinfunction "1_1") (pintype "passive"))
      (node (ref "R22") (pin "2") (pinfunction "2_2") (pintype "passive"))
      (node (ref "R238") (pin "1") (pinfunction "1_1") (pintype "passive"))
      (node (ref "R265") (pin "2") (pinfunction "2_2") (pintype "passive"))
      (node (ref "R266") (pin "2") (pinfunction "2_2") (pintype "passive"))
      (node (ref "R267") (pin "1") (pinfunction "1_1") (pintype "passive"))
      (node (ref "R268") (pin "1") (pinfunction "1_1") (pintype "passive"))
      (node (ref "R273") (pin "1") (pinfunction "1_1") (pintype "passive"))
      (node (ref "R302") (pin "1") (pinfunction "1_1") (pintype "passive"))
      (node (ref "R307") (pin "2") (pinfunction "2_2") (pintype "passive"))
      (node (ref "R324") (pin "2") (pinfunction "2_2") (pintype "passive"))
      (node (ref "R4") (pin "1") (pinfunction "1_1") (pintype "passive"))
      (node (ref "R68") (pin "2") (pinfunction "2_2") (pintype "passive"))
      (node (ref "SW1") (pin "P$1") (pinfunction "1_P$1") (pintype "bidirectional"))
      (node (ref "SW1") (pin "P$2") (pinfunction "2_P$2") (pintype "bidirectional"))
      (node (ref "U1") (pin "4") (pinfunction "GND_4") (pintype "power_in"))
      (node (ref "U101") (pin "7") (pinfunction "VSS_7") (pintype "power_in"))
      (node (ref "U121") (pin "3") (pinfunction "GND\\_3") (pintype "bidirectional"))
      (node (ref "U127") (pin "9") (pinfunction "VSS_9") (pintype "bidirectional"))
      (node (ref "U2") (pin "21") (pinfunction "GND_21") (pintype "bidirectional"))
      (node (ref "U2") (pin "3") (pinfunction "GND_3") (pintype "bidirectional"))
      (node (ref "U2") (pin "5") (pinfunction "GND_5") (pintype "bidirectional"))
      (node (ref "U28") (pin "1") (pinfunction "GND_1") (pintype "bidirectional"))
      (node (ref "U3") (pin "1") (pinfunction "GND_1") (pintype "bidirectional"))
      (node (ref "U309") (pin "2") (pinfunction "P$2_2") (pintype "bidirectional"))
      (node (ref "U4") (pin "1") (pinfunction "CLKIN_1") (pintype "bidirectional"))
      (node (ref "U4") (pin "11") (pinfunction "FSYNC_11") (pintype "bidirectional"))
      (node (ref "U4") (pin "18") (pinfunction "GND_18") (pintype "bidirectional"))
      (node (ref "U4") (pin "9") (pinfunction "AD0_9") (pintype "bidirectional"))
      (node (ref "U5") (pin "3") (pinfunction "GND_3") (pintype "bidirectional"))
      (node (ref "U6") (pin "2") (pinfunction "GND_2") (pintype "bidirectional"))
      (node (ref "U7") (pin "1") (pinfunction "GND_1") (pintype "bidirectional"))
      (node (ref "U8") (pin "P$1") (pinfunction "1_VSS_P$1") (pintype "bidirectional"))
      (node (ref "U8") (pin "P$5") (pinfunction "5_RW_P$5") (pintype "bidirectional"))
      (node (ref "X1") (pin "2") (pinfunction "GND_2") (pintype "passive"))
      (node (ref "X1") (pin "4") (pinfunction "GND_4") (pintype "passive"))
    )
    (net (code "40") (name "Net-(BUZ1-1+)") (class "Default")
      (node (ref "BUZ1") (pin "1") (pinfunction "1+_1") (pintype "bidirectional"))
      (node (ref "D004") (pin "-") (pinfunction "-_-") (pintype "passive"))
      (node (ref "R303") (pin "2") (pinfunction "2_2") (pintype "passive"))
    )
    (net (code "41") (name "Net-(BUZ1-2-)") (class "Default")
      (node (ref "BUZ1") (pin "2") (pinfunction "2-_2") (pintype "bidirectional"))
      (node (ref "D004") (pin "+") (pinfunction "+_+") (pintype "passive"))
      (node (ref "Q103") (pin "3") (pinfunction "C_3") (pintype "passive"))
    )
    (net (code "42") (name "Net-(C103-Pad1)") (class "Default")
      (node (ref "C103") (pin "1") (pinfunction "1_1") (pintype "passive"))
      (node (ref "R103") (pin "1") (pinfunction "1_1") (pintype "passive"))
    )
    (net (code "43") (name "Net-(C106-Pad+)") (class "Default")
      (node (ref "C106") (pin "+") (pinfunction "+_+") (pintype "passive"))
      (node (ref "R106") (pin "1") (pinfunction "1_1") (pintype "passive"))
    )
    (net (code "44") (name "Net-(D1-+)") (class "Default")
      (node (ref "D1") (pin "1") (pinfunction "+_1") (pintype "passive"))
      (node (ref "U1") (pin "1") (pinfunction "OUT1_1") (pintype "output"))
      (node (ref "U1") (pin "2") (pinfunction "-IN1_2") (pintype "input"))
    )
    (net (code "45") (name "Net-(D11-A)") (class "Default")
      (node (ref "D11") (pin "1") (pinfunction "A_1") (pintype "passive"))
      (node (ref "R7") (pin "2") (pinfunction "2_2") (pintype "passive"))
    )
    (net (code "46") (name "Net-(D11-C)") (class "Default")
      (node (ref "D11") (pin "2") (pinfunction "C_2") (pintype "passive"))
      (node (ref "Q1") (pin "3") (pinfunction "C_3") (pintype "passive"))
    )
    (net (code "47") (name "Net-(D12-+)") (class "Default")
      (node (ref "C15") (pin "2") (pinfunction "2_2") (pintype "passive"))
      (node (ref "C16") (pin "2") (pinfunction "2_2") (pintype "passive"))
      (node (ref "C2") (pin "2") (pinfunction "2_2") (pintype "passive"))
      (node (ref "D12") (pin "2") (pinfunction "+_2") (pintype "passive"))
      (node (ref "L2") (pin "2") (pinfunction "2_2") (pintype "passive"))
    )
    (net (code "48") (name "Net-(D13-Pad+)") (class "Default")
      (node (ref "D13") (pin "+") (pinfunction "+_+") (pintype "passive"))
      (node (ref "R3") (pin "2") (pinfunction "2_2") (pintype "passive"))
    )
    (net (code "49") (name "Net-(D14-Pad+)") (class "Default")
      (node (ref "D14") (pin "+") (pinfunction "+_+") (pintype "passive"))
      (node (ref "R6") (pin "2") (pinfunction "2_2") (pintype "passive"))
    )
    (net (code "50") (name "Net-(D130-2_K)") (class "Default")
      (node (ref "D130") (pin "2") (pinfunction "2_K_2") (pintype "passive"))
      (node (ref "R307") (pin "1") (pinfunction "1_1") (pintype "passive"))
    )
    (net (code "51") (name "Net-(J9-+)") (class "Default")
      (node (ref "C26") (pin "1") (pinfunction "1_1") (pintype "passive"))
      (node (ref "J9") (pin "2") (pinfunction "+_2") (pintype "bidirectional"))
      (node (ref "R16") (pin "1") (pinfunction "1_1") (pintype "passive"))
    )
    (net (code "52") (name "Net-(J14-2_ECHO)") (class "Default")
      (node (ref "J14") (pin "P$2") (pinfunction "2_ECHO_P$2") (pintype "bidirectional"))
      (node (ref "R299") (pin "1") (pinfunction "1_1") (pintype "passive"))
    )
    (net (code "53") (name "Net-(J101-S)") (class "Default")
      (node (ref "C101") (pin "2") (pinfunction "2_2") (pintype "passive"))
      (node (ref "J101") (pin "2") (pinfunction "S_2") (pintype "bidirectional"))
      (node (ref "R101") (pin "2") (pinfunction "2_2") (pintype "passive"))
      (node (ref "R102") (pin "2") (pinfunction "2_2") (pintype "passive"))
    )
    (net (code "54") (name "Net-(Q1-B)") (class "Default")
      (node (ref "Q1") (pin "1") (pinfunction "B_1") (pintype "passive"))
      (node (ref "R4") (pin "2") (pinfunction "2_2") (pintype "passive"))
      (node (ref "R5") (pin "1") (pinfunction "1_1") (pintype "passive"))
    )
    (net (code "55") (name "Net-(Q103-B)") (class "Default")
      (node (ref "Q103") (pin "1") (pinfunction "B_1") (pintype "passive"))
      (node (ref "R284") (pin "2") (pinfunction "2_2") (pintype "passive"))
      (node (ref "R302") (pin "2") (pinfunction "2_2") (pintype "passive"))
    )
    (net (code "56") (name "Net-(Q108-B)") (class "Default")
      (node (ref "Q108") (pin "1") (pinfunction "B_1") (pintype "passive"))
      (node (ref "R321") (pin "1") (pinfunction "1_1") (pintype "passive"))
      (node (ref "R324") (pin "1") (pinfunction "1_1") (pintype "passive"))
    )
    (net (code "57") (name "Net-(Q108-C)") (class "Default")
      (node (ref "Q108") (pin "3") (pinfunction "C_3") (pintype "passive"))
      (node (ref "U8") (pin "P$16") (pinfunction "16_LED_K_P$16") (pintype "bidirectional"))
    )
    (net (code "58") (name "Net-(Q115-B)") (class "Default")
      (node (ref "Q115") (pin "1") (pinfunction "B_1") (pintype "passive"))
      (node (ref "R273") (pin "2") (pinfunction "2_2") (pintype "passive"))
      (node (ref "R274") (pin "1") (pinfunction "1_1") (pintype "passive"))
    )
    (net (code "59") (name "Net-(R15-2)") (class "Default")
      (node (ref "C104") (pin "2") (pinfunction "2_2") (pintype "passive"))
      (node (ref "R15") (pin "2") (pinfunction "3_2") (pintype "passive"))
      (node (ref "R15") (pin "3") (pinfunction "2_3") (pintype "passive"))
      (node (ref "U101") (pin "12") (pinfunction "2OUT_12") (pintype "output"))
    )
    (net (code "60") (name "Net-(R23-3)") (class "Default")
      (node (ref "R21") (pin "2") (pinfunction "2_2") (pintype "passive"))
      (node (ref "R23") (pin "2") (pinfunction "3_2") (pintype "passive"))
      (node (ref "U1") (pin "6") (pinfunction "-IN2_6") (pintype "input"))
    )
    (net (code "61") (name "Net-(R104-Pad1)") (class "Default")
      (node (ref "R104") (pin "1") (pinfunction "1_1") (pintype "passive"))
      (node (ref "R15") (pin "1") (pinfunction "1_1") (pintype "passive"))
    )
    (net (code "62") (name "Net-(R268-3)") (class "Default")
      (node (ref "R268") (pin "2") (pinfunction "3_2") (pintype "passive"))
      (node (ref "U8") (pin "P$3") (pinfunction "3_V0_P$3") (pintype "bidirectional"))
    )
    (net (code "63") (name "Net-(U1A-+IN1)") (class "Default")
      (node (ref "R23") (pin "1") (pinfunction "1_1") (pintype "passive"))
      (node (ref "U1") (pin "3") (pinfunction "+IN1_3") (pintype "input"))
      (node (ref "U1") (pin "7") (pinfunction "OUT2_7") (pintype "output"))
    )
    (net (code "64") (name "Net-(U1B-+IN2)") (class "Default")
      (node (ref "C26") (pin "2") (pinfunction "2_2") (pintype "passive"))
      (node (ref "R20") (pin "2") (pinfunction "2_2") (pintype "passive"))
      (node (ref "U1") (pin "5") (pinfunction "+IN2_5") (pintype "input"))
    )
    (net (code "65") (name "Net-(U2-PB6(XTAL1{slash}TOSC1))") (class "Default")
      (node (ref "C4") (pin "2") (pinfunction "2_2") (pintype "passive"))
      (node (ref "U2") (pin "7") (pinfunction "PB6(XTAL1/TOSC1)_7") (pintype "bidirectional"))
      (node (ref "X1") (pin "3") (pinfunction "C2_3") (pintype "passive"))
    )
    (net (code "66") (name "Net-(U2-PB7(XTAL2{slash}TOSC2))") (class "Default")
      (node (ref "C3") (pin "2") (pinfunction "2_2") (pintype "passive"))
      (node (ref "U2") (pin "8") (pinfunction "PB7(XTAL2/TOSC2)_8") (pintype "bidirectional"))
      (node (ref "X1") (pin "1") (pinfunction "C1_1") (pintype "passive"))
    )
    (net (code "67") (name "Net-(U3-DTR#)") (class "Default")
      (node (ref "C13") (pin "1") (pinfunction "1_1") (pintype "passive"))
      (node (ref "U3") (pin "13") (pinfunction "DTR#_13") (pintype "bidirectional"))
    )
    (net (code "68") (name "Net-(U3-RXD)") (class "Default")
      (node (ref "R1") (pin "2") (pinfunction "2_2") (pintype "passive"))
      (node (ref "U3") (pin "3") (pinfunction "RXD_3") (pintype "bidirectional"))
    )
    (net (code "69") (name "Net-(U3-TXD)") (class "Default")
      (node (ref "R17") (pin "2") (pinfunction "2_2") (pintype "passive"))
      (node (ref "U3") (pin "2") (pinfunction "TXD_2") (pintype "bidirectional"))
    )
    (net (code "70") (name "Net-(U3-V3)") (class "Default")
      (node (ref "C12") (pin "1") (pinfunction "1_1") (pintype "passive"))
      (node (ref "U3") (pin "4") (pinfunction "V3_4") (pintype "bidirectional"))
    )
    (net (code "71") (name "Net-(U4-CPOUT)") (class "Default")
      (node (ref "C30") (pin "2") (pinfunction "2_2") (pintype "passive"))
      (node (ref "U4") (pin "20") (pinfunction "CPOUT_20") (pintype "bidirectional"))
    )
    (net (code "72") (name "Net-(U4-REGOUT)") (class "Default")
      (node (ref "C29") (pin "2") (pinfunction "2_2") (pintype "passive"))
      (node (ref "U4") (pin "10") (pinfunction "REGOUT_10") (pintype "bidirectional"))
    )
    (net (code "73") (name "Net-(U6-OE)") (class "Default")
      (node (ref "R10") (pin "2") (pinfunction "2_2") (pintype "passive"))
      (node (ref "R11") (pin "2") (pinfunction "2_2") (pintype "passive"))
      (node (ref "U6") (pin "6") (pinfunction "OE_6") (pintype "bidirectional"))
    )
    (net (code "74") (name "Net-(U28-EN)") (class "Default")
      (node (ref "R66") (pin "1") (pinfunction "1_1") (pintype "passive"))
      (node (ref "U28") (pin "2") (pinfunction "EN_2") (pintype "bidirectional"))
    )
    (net (code "75") (name "Net-(U28-PGND)") (class "Default")
      (node (ref "C15") (pin "1") (pinfunction "1_1") (pintype "passive"))
      (node (ref "C16") (pin "1") (pinfunction "1_1") (pintype "passive"))
      (node (ref "C2") (pin "1") (pinfunction "1_1") (pintype "passive"))
      (node (ref "L1") (pin "2") (pinfunction "2_2") (pintype "passive"))
      (node (ref "U28") (pin "3") (pinfunction "SW_3") (pintype "bidirectional"))
      (node (ref "U28") (pin "6") (pinfunction "PGND_6") (pintype "bidirectional"))
    )
    (net (code "76") (name "Net-(U101-1IN+)") (class "Default")
      (node (ref "R102") (pin "1") (pinfunction "1_1") (pintype "passive"))
      (node (ref "U101") (pin "14") (pinfunction "1IN+_14") (pintype "input"))
    )
    (net (code "77") (name "Net-(U101-1IN-)") (class "Default")
      (node (ref "C105") (pin "2") (pinfunction "2_2") (pintype "passive"))
      (node (ref "R105") (pin "2") (pinfunction "2_2") (pintype "passive"))
      (node (ref "R106") (pin "2") (pinfunction "2_2") (pintype "passive"))
      (node (ref "U101") (pin "15") (pinfunction "1IN-_15") (pintype "input"))
    )
    (net (code "78") (name "Net-(U101-1OUT)") (class "Default")
      (node (ref "C103") (pin "2") (pinfunction "2_2") (pintype "passive"))
      (node (ref "C105") (pin "1") (pinfunction "1_1") (pintype "passive"))
      (node (ref "R105") (pin "1") (pinfunction "1_1") (pintype "passive"))
      (node (ref "U101") (pin "16") (pinfunction "1OUT_16") (pintype "output"))
    )
    (net (code "79") (name "Net-(U101-2IN-)") (class "Default")
      (node (ref "C104") (pin "1") (pinfunction "1_1") (pintype "passive"))
      (node (ref "R103") (pin "2") (pinfunction "2_2") (pintype "passive"))
      (node (ref "R104") (pin "2") (pinfunction "2_2") (pintype "passive"))
      (node (ref "U101") (pin "13") (pinfunction "2IN-_13") (pintype "input"))
    )
    (net (code "80") (name "Net-(U101-A)") (class "Default")
      (node (ref "R113") (pin "2") (pinfunction "2_2") (pintype "passive"))
      (node (ref "U101") (pin "1") (pinfunction "A_1") (pintype "bidirectional"))
    )
    (net (code "81") (name "Net-(U101-IB)") (class "Default")
      (node (ref "R108") (pin "2") (pinfunction "2_2") (pintype "passive"))
      (node (ref "U101") (pin "10") (pinfunction "IB_10") (pintype "bidirectional"))
    )
    (net (code "82") (name "Net-(U101-RC1)") (class "Default")
      (node (ref "C108") (pin "1") (pinfunction "1_1") (pintype "passive"))
      (node (ref "R111") (pin "2") (pinfunction "2_2") (pintype "passive"))
      (node (ref "U101") (pin "4") (pinfunction "RC1_4") (pintype "bidirectional"))
    )
    (net (code "83") (name "Net-(U101-RC2)") (class "Default")
      (node (ref "C107") (pin "1") (pinfunction "1_1") (pintype "passive"))
      (node (ref "R110") (pin "1") (pinfunction "1_1") (pintype "passive"))
      (node (ref "U101") (pin "5") (pinfunction "RC2_5") (pintype "bidirectional"))
    )
    (net (code "84") (name "Net-(U101-RR1)") (class "Default")
      (node (ref "R111") (pin "1") (pinfunction "1_1") (pintype "passive"))
      (node (ref "U101") (pin "3") (pinfunction "RR1_3") (pintype "bidirectional"))
    )
    (net (code "85") (name "Net-(U101-RR2)") (class "Default")
      (node (ref "R110") (pin "2") (pinfunction "2_2") (pintype "passive"))
      (node (ref "U101") (pin "6") (pinfunction "RR2_6") (pintype "bidirectional"))
    )
    (net (code "86") (name "Net-(U101-VC)") (class "Default")
      (node (ref "R109") (pin "2") (pinfunction "2_2") (pintype "passive"))
      (node (ref "U101") (pin "9") (pinfunction "VC_9") (pintype "bidirectional"))
    )
    (net (code "87") (name "Net-(U101-VO)") (class "Default")
      (node (ref "R112") (pin "2") (pinfunction "2_2") (pintype "passive"))
      (node (ref "U101") (pin "2") (pinfunction "VO_2") (pintype "bidirectional"))
    )
    (net (code "88") (name "Net-(U121-ADDR)") (class "Default")
      (node (ref "R237") (pin "1") (pinfunction "1_1") (pintype "passive"))
      (node (ref "R238") (pin "2") (pinfunction "2_2") (pintype "passive"))
      (node (ref "U121") (pin "2") (pinfunction "ADDR_2") (pintype "bidirectional"))
    )
    (net (code "89") (name "Net-(U121-DVI)") (class "Default")
      (node (ref "C209") (pin "2") (pinfunction "2_2") (pintype "passive"))
      (node (ref "R271") (pin "2") (pinfunction "2_2") (pintype "passive"))
      (node (ref "U121") (pin "5") (pinfunction "DVI_5") (pintype "bidirectional"))
    )
    (net (code "90") (name "Net-(U127-A0)") (class "Default")
      (node (ref "R263") (pin "2") (pinfunction "2_2") (pintype "passive"))
      (node (ref "R267") (pin "2") (pinfunction "2_2") (pintype "passive"))
      (node (ref "U127") (pin "5") (pinfunction "A0_5") (pintype "bidirectional"))
    )
    (net (code "91") (name "Net-(U127-A1)") (class "Default")
      (node (ref "R262") (pin "1") (pinfunction "1_1") (pintype "passive"))
      (node (ref "R266") (pin "1") (pinfunction "1_1") (pintype "passive"))
      (node (ref "U127") (pin "4") (pinfunction "A1_4") (pintype "bidirectional"))
    )
    (net (code "92") (name "Net-(U127-A2)") (class "Default")
      (node (ref "R261") (pin "1") (pinfunction "1_1") (pintype "passive"))
      (node (ref "R265") (pin "1") (pinfunction "1_1") (pintype "passive"))
      (node (ref "U127") (pin "3") (pinfunction "A2_3") (pintype "bidirectional"))
    )
    (net (code "93") (name "Net-(U127-~{RESET})") (class "Default")
      (node (ref "R264") (pin "2") (pinfunction "2_2") (pintype "passive"))
      (node (ref "U127") (pin "6") (pinfunction "~{RESET}_6") (pintype "bidirectional"))
    )
    (net (code "94") (name "RESET") (class "Default")
      (node (ref "C13") (pin "2") (pinfunction "2_2") (pintype "passive"))
      (node (ref "C23") (pin "2") (pinfunction "2_2") (pintype "passive"))
      (node (ref "ICSP") (pin "3") (pinfunction "3_3") (pintype "bidirectional"))
      (node (ref "R14") (pin "2") (pinfunction "2_2") (pintype "passive"))
      (node (ref "SW1") (pin "P$3") (pinfunction "3_P$3") (pintype "bidirectional"))
      (node (ref "SW1") (pin "P$4") (pinfunction "4_P$4") (pintype "bidirectional"))
      (node (ref "U2") (pin "29") (pinfunction "PC6(/RESET)_29") (pintype "bidirectional"))
    )
    (net (code "95") (name "SEN_3V3") (class "Default")
      (node (ref "C102") (pin "2") (pinfunction "2_2") (pintype "passive"))
      (node (ref "C14") (pin "2") (pinfunction "2_2") (pintype "passive"))
      (node (ref "C17") (pin "1") (pinfunction "1_1") (pintype "passive"))
      (node (ref "C22") (pin "1") (pinfunction "1_1") (pintype "passive"))
      (node (ref "C31") (pin "2") (pinfunction "2_2") (pintype "passive"))
      (node (ref "C34") (pin "1") (pinfunction "1_1") (pintype "passive"))
      (node (ref "J101") (pin "1") (pinfunction "D_1") (pintype "bidirectional"))
      (node (ref "R109") (pin "1") (pinfunction "1_1") (pintype "passive"))
      (node (ref "R11") (pin "1") (pinfunction "1_1") (pintype "passive"))
      (node (ref "R113") (pin "1") (pinfunction "1_1") (pintype "passive"))
      (node (ref "R12") (pin "1") (pinfunction "1_1") (pintype "passive"))
      (node (ref "R13") (pin "1") (pinfunction "1_1") (pintype "passive"))
      (node (ref "R237") (pin "2") (pinfunction "2_2") (pintype "passive"))
      (node (ref "R271") (pin "1") (pinfunction "1_1") (pintype "passive"))
      (node (ref "U101") (pin "11") (pinfunction "VDD_11") (pintype "power_in"))
      (node (ref "U101") (pin "8") (pinfunction "~{RESET}_8") (pintype "input"))
      (node (ref "U121") (pin "1") (pinfunction "VCC_1") (pintype "bidirectional"))
      (node (ref "U4") (pin "13") (pinfunction "VDD_13") (pintype "bidirectional"))
      (node (ref "U4") (pin "8") (pinfunction "VLOGIC_8") (pintype "bidirectional"))
      (node (ref "U6") (pin "3") (pinfunction "VCCA_3") (pintype "bidirectional"))
      (node (ref "U7") (pin "2") (pinfunction "VOUT_2") (pintype "bidirectional"))
      (node (ref "U7") (pin "4") (pinfunction "TAB_4") (pintype "bidirectional"))
    )
    (net (code "96") (name "USB_DN") (class "Default")
      (node (ref "J6") (pin "1") (pinfunction "1_1") (pintype "bidirectional"))
      (node (ref "J8") (pin "3") (pinfunction "3_3") (pintype "bidirectional"))
      (node (ref "U3") (pin "6") (pinfunction "UD-_6") (pintype "bidirectional"))
    )
    (net (code "97") (name "USB_DP") (class "Default")
      (node (ref "J5") (pin "1") (pinfunction "1_1") (pintype "bidirectional"))
      (node (ref "J8") (pin "2") (pinfunction "2_2") (pintype "bidirectional"))
      (node (ref "U3") (pin "5") (pinfunction "UD+_5") (pintype "bidirectional"))
    )
    (net (code "98") (name "VCC_5V") (class "Default")
      (node (ref "C1") (pin "1+") (pinfunction "1+_1+") (pintype "bidirectional"))
      (node (ref "C11") (pin "2") (pinfunction "2_2") (pintype "passive"))
      (node (ref "C18") (pin "2") (pinfunction "2_2") (pintype "passive"))
      (node (ref "C19") (pin "1") (pinfunction "1_1") (pintype "passive"))
      (node (ref "C20") (pin "1") (pinfunction "1_1") (pintype "passive"))
      (node (ref "C21") (pin "1") (pinfunction "1_1") (pintype "passive"))
      (node (ref "C214") (pin "2") (pinfunction "2_2") (pintype "passive"))
      (node (ref "C230") (pin "2") (pinfunction "2_2") (pintype "passive"))
      (node (ref "C25") (pin "2") (pinfunction "2_2") (pintype "passive"))
      (node (ref "C33") (pin "1") (pinfunction "1_1") (pintype "passive"))
      (node (ref "C35") (pin "2") (pinfunction "2_2") (pintype "passive"))
      (node (ref "C37") (pin "2") (pinfunction "2_2") (pintype "passive"))
      (node (ref "C5") (pin "2") (pinfunction "2_2") (pintype "passive"))
      (node (ref "C66") (pin "2") (pinfunction "2_2") (pintype "passive"))
      (node (ref "C7") (pin "2") (pinfunction "2_2") (pintype "passive"))
      (node (ref "C9") (pin "2") (pinfunction "2_2") (pintype "passive"))
      (node (ref "D12") (pin "1") (pinfunction "-_1") (pintype "passive"))
      (node (ref "D130") (pin "1") (pinfunction "1_A_1") (pintype "passive"))
      (node (ref "ICSP") (pin "6") (pinfunction "6_6") (pintype "bidirectional"))
      (node (ref "J1") (pin "2") (pinfunction "2_2") (pintype "bidirectional"))
      (node (ref "J10") (pin "2") (pinfunction "2_2") (pintype "bidirectional"))
      (node (ref "J11") (pin "2") (pinfunction "2_2") (pintype "bidirectional"))
      (node (ref "J12") (pin "2") (pinfunction "2_2") (pintype "bidirectional"))
      (node (ref "J13") (pin "2") (pinfunction "2_2") (pintype "bidirectional"))
      (node (ref "J14") (pin "P$4") (pinfunction "4VCC_P$4") (pintype "bidirectional"))
      (node (ref "J2") (pin "2") (pinfunction "2_2") (pintype "bidirectional"))
      (node (ref "J3") (pin "3") (pinfunction "3_3") (pintype "bidirectional"))
      (node (ref "L11") (pin "1") (pinfunction "1_1") (pintype "bidirectional"))
      (node (ref "P1") (pin "3") (pinfunction "2_3") (pintype "passive"))
      (node (ref "R14") (pin "1") (pinfunction "1_1") (pintype "passive"))
      (node (ref "R16") (pin "2") (pinfunction "2_2") (pintype "passive"))
      (node (ref "R18") (pin "1") (pinfunction "1_1") (pintype "passive"))
      (node (ref "R19") (pin "1") (pinfunction "1_1") (pintype "passive"))
      (node (ref "R2") (pin "1") (pinfunction "1_1") (pintype "passive"))
      (node (ref "R261") (pin "2") (pinfunction "2_2") (pintype "passive"))
      (node (ref "R262") (pin "2") (pinfunction "2_2") (pintype "passive"))
      (node (ref "R263") (pin "1") (pinfunction "1_1") (pintype "passive"))
      (node (ref "R264") (pin "1") (pinfunction "1_1") (pintype "passive"))
      (node (ref "R268") (pin "3") (pinfunction "2_3") (pintype "passive"))
      (node (ref "R3") (pin "1") (pinfunction "1_1") (pintype "passive"))
      (node (ref "R301") (pin "1") (pinfunction "1_1") (pintype "passive"))
      (node (ref "R303") (pin "1") (pinfunction "1_1") (pintype "passive"))
      (node (ref "R6") (pin "1") (pinfunction "1_1") (pintype "passive"))
      (node (ref "R67") (pin "1") (pinfunction "1_1") (pintype "passive"))
      (node (ref "R7") (pin "1") (pinfunction "1_1") (pintype "passive"))
      (node (ref "R8") (pin "1") (pinfunction "1_1") (pintype "passive"))
      (node (ref "R9") (pin "1") (pinfunction "1_1") (pintype "passive"))
      (node (ref "U1") (pin "8") (pinfunction "+V_8") (pintype "power_in"))
      (node (ref "U127") (pin "20") (pinfunction "VDD_20") (pintype "bidirectional"))
      (node (ref "U2") (pin "18") (pinfunction "AVCC_18") (pintype "bidirectional"))
      (node (ref "U2") (pin "4") (pinfunction "VCC_4") (pintype "bidirectional"))
      (node (ref "U2") (pin "6") (pinfunction "VCC_6") (pintype "bidirectional"))
      (node (ref "U3") (pin "16") (pinfunction "VCC_16") (pintype "bidirectional"))
      (node (ref "U309") (pin "1") (pinfunction "P$1_1") (pintype "bidirectional"))
      (node (ref "U5") (pin "1") (pinfunction "VCC_1") (pintype "bidirectional"))
      (node (ref "U6") (pin "7") (pinfunction "VCCB_7") (pintype "bidirectional"))
      (node (ref "U7") (pin "3") (pinfunction "VIN_3") (pintype "bidirectional"))
      (node (ref "U8") (pin "P$15") (pinfunction "15_LEDA_P$15") (pintype "bidirectional"))
      (node (ref "U8") (pin "P$2") (pinfunction "2_VDD_P$2") (pintype "bidirectional"))
    )
    (net (code "99") (name "VFB") (class "Default")
      (node (ref "C66") (pin "1") (pinfunction "1_1") (pintype "passive"))
      (node (ref "R67") (pin "2") (pinfunction "2_2") (pintype "passive"))
      (node (ref "R68") (pin "1") (pinfunction "1_1") (pintype "passive"))
      (node (ref "U28") (pin "5") (pinfunction "FB_5") (pintype "bidirectional"))
    )
    (net (code "100") (name "VIN") (class "Default")
      (node (ref "C24") (pin "1+") (pinfunction "1+_1+") (pintype "bidirectional"))
      (node (ref "C6") (pin "2") (pinfunction "2_2") (pintype "passive"))
      (node (ref "J4") (pin "1") (pinfunction "1_1") (pintype "bidirectional"))
      (node (ref "J8") (pin "1") (pinfunction "1_1") (pintype "bidirectional"))
      (node (ref "L1") (pin "1") (pinfunction "1_1") (pintype "passive"))
      (node (ref "R66") (pin "2") (pinfunction "2_2") (pintype "passive"))
      (node (ref "U28") (pin "4") (pinfunction "VIN_4") (pintype "bidirectional"))
    )
    (net (code "101") (name "unconnected-(J1-Pad3)") (class "Default")
      (node (ref "J1") (pin "3") (pinfunction "3_3") (pintype "bidirectional"))
    )
    (net (code "102") (name "unconnected-(J3-Pad2)") (class "Default")
      (node (ref "J3") (pin "2") (pinfunction "2_2") (pintype "bidirectional"))
    )
    (net (code "103") (name "unconnected-(J12-Pad3)") (class "Default")
      (node (ref "J12") (pin "3") (pinfunction "3_3") (pintype "bidirectional"))
    )
    (net (code "104") (name "unconnected-(J13-Pad3)") (class "Default")
      (node (ref "J13") (pin "3") (pinfunction "3_3") (pintype "bidirectional"))
    )
    (net (code "105") (name "unconnected-(K1-Pad2)") (class "Default")
      (node (ref "K1") (pin "2") (pinfunction "2_2") (pintype "bidirectional"))
    )
    (net (code "106") (name "unconnected-(K1-Pad3)") (class "Default")
      (node (ref "K1") (pin "3") (pinfunction "3_3") (pintype "bidirectional"))
    )
    (net (code "107") (name "unconnected-(R23-2-Pad3)") (class "Default")
      (node (ref "R23") (pin "3") (pinfunction "2_3") (pintype "passive"))
    )
    (net (code "108") (name "unconnected-(U3-CTS#-Pad9)") (class "Default")
      (node (ref "U3") (pin "9") (pinfunction "CTS#_9") (pintype "bidirectional"))
    )
    (net (code "109") (name "unconnected-(U3-DCD#-Pad12)") (class "Default")
      (node (ref "U3") (pin "12") (pinfunction "DCD#_12") (pintype "bidirectional"))
    )
    (net (code "110") (name "unconnected-(U3-DSR#-Pad10)") (class "Default")
      (node (ref "U3") (pin "10") (pinfunction "DSR#_10") (pintype "bidirectional"))
    )
    (net (code "111") (name "unconnected-(U3-RI#-Pad11)") (class "Default")
      (node (ref "U3") (pin "11") (pinfunction "RI#_11") (pintype "bidirectional"))
    )
    (net (code "112") (name "unconnected-(U3-RS232-Pad15)") (class "Default")
      (node (ref "U3") (pin "15") (pinfunction "RS232_15") (pintype "bidirectional"))
    )
    (net (code "113") (name "unconnected-(U3-RTS#-Pad14)") (class "Default")
      (node (ref "U3") (pin "14") (pinfunction "RTS#_14") (pintype "bidirectional"))
    )
    (net (code "114") (name "unconnected-(U3-XI-Pad7)") (class "Default")
      (node (ref "U3") (pin "7") (pinfunction "XI_7") (pintype "bidirectional"))
    )
    (net (code "115") (name "unconnected-(U3-XO-Pad8)") (class "Default")
      (node (ref "U3") (pin "8") (pinfunction "XO_8") (pintype "bidirectional"))
    )
    (net (code "116") (name "unconnected-(U4-AUX_CL-Pad7)") (class "Default")
      (node (ref "U4") (pin "7") (pinfunction "AUX_CL_7") (pintype "bidirectional"))
    )
    (net (code "117") (name "unconnected-(U4-AUX_DA-Pad6)") (class "Default")
      (node (ref "U4") (pin "6") (pinfunction "AUX_DA_6") (pintype "bidirectional"))
    )
    (net (code "118") (name "unconnected-(U4-INT-Pad12)") (class "Default")
      (node (ref "U4") (pin "12") (pinfunction "INT_12") (pintype "bidirectional"))
    )
    (net (code "119") (name "unconnected-(U8-7_D0-PadP$7)") (class "Default")
      (node (ref "U8") (pin "P$7") (pinfunction "7_D0_P$7") (pintype "bidirectional"))
    )
    (net (code "120") (name "unconnected-(U8-8_D1-PadP$8)") (class "Default")
      (node (ref "U8") (pin "P$8") (pinfunction "8_D1_P$8") (pintype "bidirectional"))
    )
    (net (code "121") (name "unconnected-(U8-9_D2-PadP$9)") (class "Default")
      (node (ref "U8") (pin "P$9") (pinfunction "9_D2_P$9") (pintype "bidirectional"))
    )
    (net (code "122") (name "unconnected-(U8-10_D3-PadP$10)") (class "Default")
      (node (ref "U8") (pin "P$10") (pinfunction "10_D3_P$10") (pintype "bidirectional"))
    )
    (net (code "123") (name "unconnected-(U127-GP0-Pad12)") (class "Default")
      (node (ref "U127") (pin "12") (pinfunction "GP0_12") (pintype "bidirectional"))
    )
    (net (code "124") (name "unconnected-(U127-INT-Pad8)") (class "Default")
      (node (ref "U127") (pin "8") (pinfunction "INT_8") (pintype "bidirectional"))
    )
    (net (code "125") (name "unconnected-(U127-NC0-Pad7)") (class "Default")
      (node (ref "U127") (pin "7") (pinfunction "NC0_7") (pintype "bidirectional"))
    )
    (net (code "126") (name "unconnected-(U127-NC1-Pad10)") (class "Default")
      (node (ref "U127") (pin "10") (pinfunction "NC1_10") (pintype "bidirectional"))
    )
    (net (code "127") (name "unconnected-(U127-NC2-Pad11)") (class "Default")
      (node (ref "U127") (pin "11") (pinfunction "NC2_11") (pintype "bidirectional"))
    )
  )
)
